# Datalogger_Shield_RTC.net
KiCad netlist of a schematic drawn in EAGLE
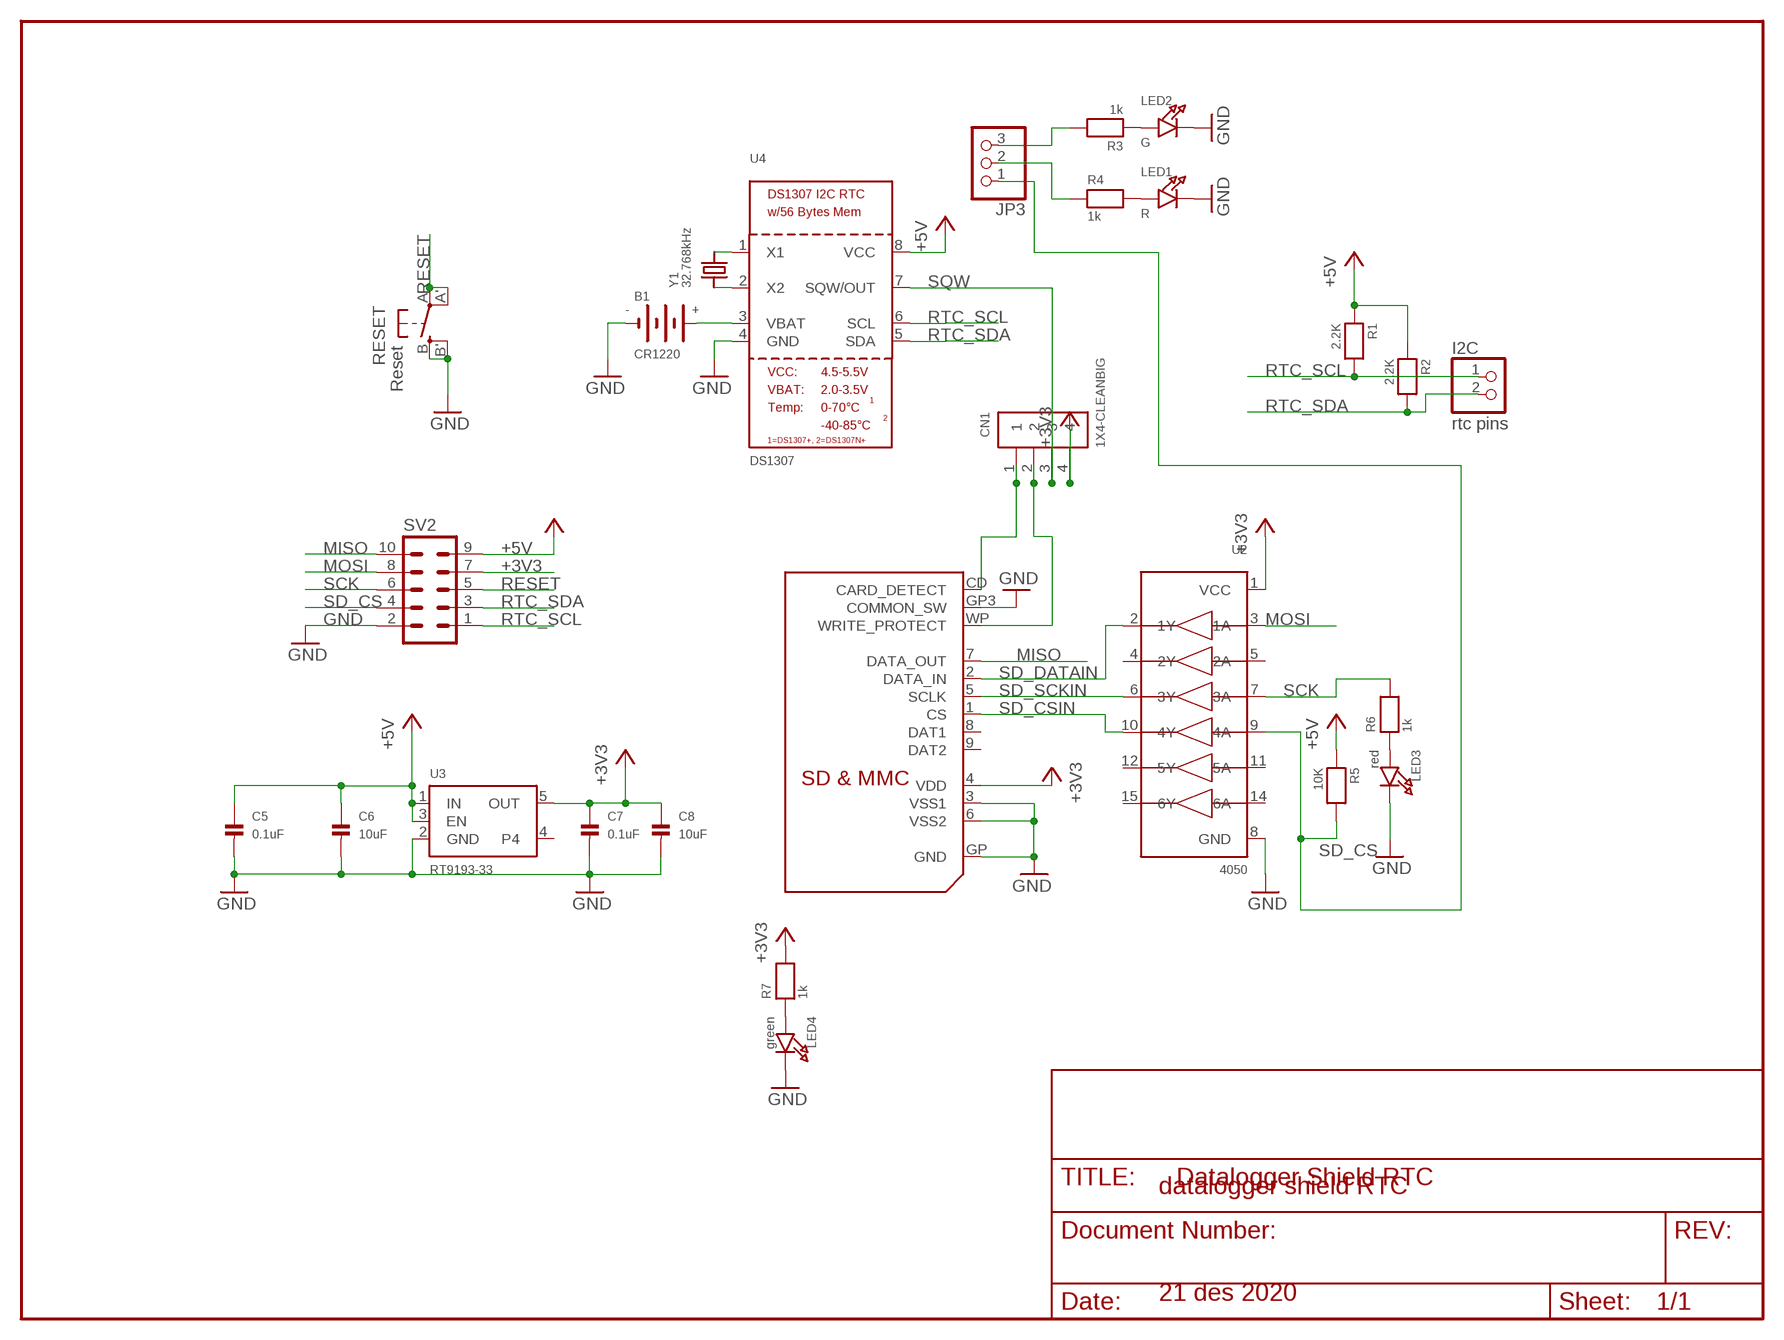
[diagram p0: schematic, sheet 1]

(export (version "E")
  (design (tool "Eeschema 10.0.6"))
  (components
    (comp (ref "B1")
      (value "CR1220")
      (footprint "eagle-import:CR1220")
      (libsource (lib "eagle-import") (part "BATTERYCR1220_SMT"))
    )
    (comp (ref "C5")
      (value "0.1uF")
      (footprint "eagle-import:0805")
      (libsource (lib "eagle-import") (part "CAP_CERAMIC0805"))
    )
    (comp (ref "C6")
      (value "10uF")
      (footprint "eagle-import:0805")
      (libsource (lib "eagle-import") (part "CAP_CERAMIC0805"))
    )
    (comp (ref "C7")
      (value "0.1uF")
      (footprint "eagle-import:0805")
      (libsource (lib "eagle-import") (part "CAP_CERAMIC0805"))
    )
    (comp (ref "C8")
      (value "10uF")
      (footprint "eagle-import:0805")
      (libsource (lib "eagle-import") (part "CAP_CERAMIC0805"))
    )
    (comp (ref "CN1")
      (value "1X4-CLEANBIG")
      (footprint "eagle-import:1X04-CLEANBIG")
      (libsource (lib "eagle-import") (part "1X4-CLEANBIG"))
    )
    (comp (ref "I2C")
      (value "rtc pins")
      (footprint "eagle-import:1X02")
      (libsource (lib "eagle-import") (part "PINHD-1X2"))
    )
    (comp (ref "JP3")
      (value "HEADER-1X3ROUND")
      (footprint "eagle-import:1X03_ROUND")
      (libsource (lib "eagle-import") (part "HEADER-1X3ROUND"))
    )
    (comp (ref "LED1")
      (value "R")
      (footprint "eagle-import:CHIPLED_0805")
      (libsource (lib "eagle-import") (part "LED0805"))
    )
    (comp (ref "LED2")
      (value "G")
      (footprint "eagle-import:CHIPLED_0805")
      (libsource (lib "eagle-import") (part "LED0805"))
    )
    (comp (ref "LED3")
      (value "red")
      (footprint "eagle-import:CHIPLED_0805")
      (libsource (lib "eagle-import") (part "LED0805"))
    )
    (comp (ref "LED4")
      (value "green")
      (footprint "eagle-import:CHIPLED_0805")
      (libsource (lib "eagle-import") (part "LED0805"))
    )
    (comp (ref "R1")
      (value "2.2K")
      (footprint "eagle-import:0805")
      (libsource (lib "eagle-import") (part "RESISTOR0805"))
    )
    (comp (ref "R2")
      (value "2.2K")
      (footprint "eagle-import:0805")
      (libsource (lib "eagle-import") (part "RESISTOR0805"))
    )
    (comp (ref "R3")
      (value "1k")
      (footprint "eagle-import:0805")
      (libsource (lib "eagle-import") (part "RESISTOR0805"))
    )
    (comp (ref "R4")
      (value "1k")
      (footprint "eagle-import:0805")
      (libsource (lib "eagle-import") (part "RESISTOR0805"))
    )
    (comp (ref "R5")
      (value "10K")
      (footprint "eagle-import:0805")
      (libsource (lib "eagle-import") (part "RESISTOR0805"))
    )
    (comp (ref "R6")
      (value "1k")
      (footprint "eagle-import:0805")
      (libsource (lib "eagle-import") (part "RESISTOR0805"))
    )
    (comp (ref "R7")
      (value "1k")
      (footprint "eagle-import:0805")
      (libsource (lib "eagle-import") (part "RESISTOR0805"))
    )
    (comp (ref "RESET")
      (value "Reset")
      (footprint "eagle-import:EVQ-Q2")
      (libsource (lib "eagle-import") (part "SPST_TACT-EVQQ2"))
    )
    (comp (ref "SV2")
      (value "MA05-2")
      (footprint "eagle-import:MA05-2")
      (libsource (lib "eagle-import") (part "MA05-2"))
    )
    (comp (ref "U$2")
      (value "SDMMC06132")
      (footprint "eagle-import:06132")
      (libsource (lib "eagle-import") (part "SDMMC06132"))
    )
    (comp (ref "U2")
      (value "4050")
      (footprint "eagle-import:SOIC16")
      (libsource (lib "eagle-import") (part "74HC4050D"))
    )
    (comp (ref "U3")
      (value "RT9193-33")
      (footprint "eagle-import:SOT23-5")
      (libsource (lib "eagle-import") (part "VREG_SOT23-5"))
    )
    (comp (ref "U4")
      (value "DS1307")
      (footprint "eagle-import:SOIC8_150MIL")
      (fields (field (name "SPICEPREFIX") "X"))
      (libsource (lib "eagle-import") (part "RTC_DS1307"))
    )
    (comp (ref "Y1")
      (value "32.768kHz")
      (footprint "eagle-import:CRYSTAL_8X3.8")
      (libsource (lib "eagle-import") (part "CRYSTAL8X3.8SMT"))
    )
  )
  (nets
    (net (code "1") (name "+3V3") (class "Default")
      (node (ref "C7") (pin "1") (pinfunction "P$1_1") (pintype "passive"))
      (node (ref "C8") (pin "1") (pinfunction "P$1_1") (pintype "passive"))
      (node (ref "CN1") (pin "4") (pinfunction "4_4") (pintype "bidirectional"))
      (node (ref "R7") (pin "2") (pinfunction "2_2") (pintype "passive"))
      (node (ref "SV2") (pin "7") (pinfunction "7_7") (pintype "passive"))
      (node (ref "U$2") (pin "4") (pinfunction "VDD_4") (pintype "power_in"))
      (node (ref "U2") (pin "1") (pinfunction "VCC_1") (pintype "bidirectional"))
      (node (ref "U3") (pin "5") (pinfunction "OUT_5") (pintype "bidirectional"))
    )
    (net (code "2") (name "+5V") (class "Default")
      (node (ref "C5") (pin "1") (pinfunction "P$1_1") (pintype "passive"))
      (node (ref "C6") (pin "1") (pinfunction "P$1_1") (pintype "passive"))
      (node (ref "R1") (pin "1") (pinfunction "1_1") (pintype "passive"))
      (node (ref "R2") (pin "1") (pinfunction "1_1") (pintype "passive"))
      (node (ref "R5") (pin "1") (pinfunction "1_1") (pintype "passive"))
      (node (ref "SV2") (pin "9") (pinfunction "9_9") (pintype "passive"))
      (node (ref "U3") (pin "1") (pinfunction "IN_1") (pintype "bidirectional"))
      (node (ref "U3") (pin "3") (pinfunction "EN_3") (pintype "bidirectional"))
      (node (ref "U4") (pin "8") (pinfunction "VCC_8") (pintype "bidirectional"))
    )
    (net (code "3") (name "/MISO") (class "Default")
      (node (ref "SV2") (pin "10") (pinfunction "10_10") (pintype "passive"))
      (node (ref "U$2") (pin "7") (pinfunction "DATA_OUT_7") (pintype "output"))
    )
    (net (code "4") (name "/MOSI") (class "Default")
      (node (ref "SV2") (pin "8") (pinfunction "8_8") (pintype "passive"))
      (node (ref "U2") (pin "3") (pinfunction "1A_3") (pintype "bidirectional"))
    )
    (net (code "5") (name "/RESET") (class "Default")
      (node (ref "RESET") (pin "A") (pinfunction "P_A") (pintype "passive"))
      (node (ref "RESET") (pin "A'") (pinfunction "P1_A'") (pintype "passive"))
      (node (ref "SV2") (pin "5") (pinfunction "5_5") (pintype "passive"))
    )
    (net (code "6") (name "/RTC_SCL") (class "Default")
      (node (ref "I2C") (pin "1") (pinfunction "1_1") (pintype "passive"))
      (node (ref "R1") (pin "2") (pinfunction "2_2") (pintype "passive"))
      (node (ref "SV2") (pin "1") (pinfunction "1_1") (pintype "passive"))
      (node (ref "U4") (pin "6") (pinfunction "SCL_6") (pintype "bidirectional"))
    )
    (net (code "7") (name "/RTC_SDA") (class "Default")
      (node (ref "I2C") (pin "2") (pinfunction "2_2") (pintype "passive"))
      (node (ref "R2") (pin "2") (pinfunction "2_2") (pintype "passive"))
      (node (ref "SV2") (pin "3") (pinfunction "3_3") (pintype "passive"))
      (node (ref "U4") (pin "5") (pinfunction "SDA_5") (pintype "bidirectional"))
    )
    (net (code "8") (name "/SCK") (class "Default")
      (node (ref "R6") (pin "2") (pinfunction "2_2") (pintype "passive"))
      (node (ref "SV2") (pin "6") (pinfunction "6_6") (pintype "passive"))
      (node (ref "U2") (pin "7") (pinfunction "3A_7") (pintype "bidirectional"))
    )
    (net (code "9") (name "/SD_CS") (class "Default")
      (node (ref "JP3") (pin "1") (pinfunction "1_1") (pintype "passive"))
      (node (ref "R5") (pin "2") (pinfunction "2_2") (pintype "passive"))
      (node (ref "SV2") (pin "4") (pinfunction "4_4") (pintype "passive"))
      (node (ref "U2") (pin "9") (pinfunction "4A_9") (pintype "bidirectional"))
    )
    (net (code "10") (name "/SD_CSIN") (class "Default")
      (node (ref "U$2") (pin "1") (pinfunction "CS_1") (pintype "input"))
      (node (ref "U2") (pin "10") (pinfunction "4Y_10") (pintype "bidirectional"))
    )
    (net (code "11") (name "/SD_DATAIN") (class "Default")
      (node (ref "U$2") (pin "2") (pinfunction "DATA_IN_2") (pintype "input"))
      (node (ref "U2") (pin "2") (pinfunction "1Y_2") (pintype "bidirectional"))
    )
    (net (code "12") (name "/SD_SCKIN") (class "Default")
      (node (ref "U$2") (pin "5") (pinfunction "SCLK_5") (pintype "input"))
      (node (ref "U2") (pin "6") (pinfunction "3Y_6") (pintype "bidirectional"))
    )
    (net (code "13") (name "/SQW") (class "Default")
      (node (ref "CN1") (pin "3") (pinfunction "3_3") (pintype "bidirectional"))
      (node (ref "U4") (pin "7") (pinfunction "SQW/OUT_7") (pintype "bidirectional"))
    )
    (net (code "14") (name "GND") (class "Default")
      (node (ref "B1") (pin "-") (pinfunction "-_-") (pintype "passive"))
      (node (ref "C5") (pin "2") (pinfunction "P$2_2") (pintype "passive"))
      (node (ref "C6") (pin "2") (pinfunction "P$2_2") (pintype "passive"))
      (node (ref "C7") (pin "2") (pinfunction "P$2_2") (pintype "passive"))
      (node (ref "C8") (pin "2") (pinfunction "P$2_2") (pintype "passive"))
      (node (ref "LED1") (pin "C") (pinfunction "C_C") (pintype "passive"))
      (node (ref "LED2") (pin "C") (pinfunction "C_C") (pintype "passive"))
      (node (ref "LED3") (pin "C") (pinfunction "C_C") (pintype "passive"))
      (node (ref "LED4") (pin "C") (pinfunction "C_C") (pintype "passive"))
      (node (ref "RESET") (pin "B") (pinfunction "S_B") (pintype "passive"))
      (node (ref "RESET") (pin "B'") (pinfunction "S1_B'") (pintype "passive"))
      (node (ref "SV2") (pin "2") (pinfunction "2_2") (pintype "passive"))
      (node (ref "U$2") (pin "3") (pinfunction "VSS1_3") (pintype "power_in"))
      (node (ref "U$2") (pin "6") (pinfunction "VSS2_6") (pintype "power_in"))
      (node (ref "U$2") (pin "GP") (pinfunction "GND_GP") (pintype "power_in"))
      (node (ref "U$2") (pin "GP3") (pinfunction "COMMON_SW_GP3") (pintype "passive"))
      (node (ref "U2") (pin "8") (pinfunction "GND_8") (pintype "bidirectional"))
      (node (ref "U3") (pin "2") (pinfunction "GND_2") (pintype "bidirectional"))
      (node (ref "U4") (pin "4") (pinfunction "GND_4") (pintype "bidirectional"))
    )
    (net (code "15") (name "Net-(B1-+)") (class "Default")
      (node (ref "B1") (pin "+$1") (pinfunction "+_+$1") (pintype "passive"))
      (node (ref "U4") (pin "3") (pinfunction "VBAT_3") (pintype "bidirectional"))
    )
    (net (code "16") (name "Net-(JP3-Pad2)") (class "Default")
      (node (ref "JP3") (pin "2") (pinfunction "2_2") (pintype "passive"))
      (node (ref "R4") (pin "1") (pinfunction "1_1") (pintype "passive"))
    )
    (net (code "17") (name "Net-(JP3-Pad3)") (class "Default")
      (node (ref "JP3") (pin "3") (pinfunction "3_3") (pintype "passive"))
      (node (ref "R3") (pin "2") (pinfunction "2_2") (pintype "passive"))
    )
    (net (code "18") (name "Net-(LED1-PadA)") (class "Default")
      (node (ref "LED1") (pin "A") (pinfunction "A_A") (pintype "passive"))
      (node (ref "R4") (pin "2") (pinfunction "2_2") (pintype "passive"))
    )
    (net (code "19") (name "Net-(LED2-PadA)") (class "Default")
      (node (ref "LED2") (pin "A") (pinfunction "A_A") (pintype "passive"))
      (node (ref "R3") (pin "1") (pinfunction "1_1") (pintype "passive"))
    )
    (net (code "20") (name "Net-(LED3-PadA)") (class "Default")
      (node (ref "LED3") (pin "A") (pinfunction "A_A") (pintype "passive"))
      (node (ref "R6") (pin "1") (pinfunction "1_1") (pintype "passive"))
    )
    (net (code "21") (name "Net-(LED4-PadA)") (class "Default")
      (node (ref "LED4") (pin "A") (pinfunction "A_A") (pintype "passive"))
      (node (ref "R7") (pin "1") (pinfunction "1_1") (pintype "passive"))
    )
    (net (code "22") (name "Net-(U$2-CARD_DETECT)") (class "Default")
      (node (ref "CN1") (pin "1") (pinfunction "1_1") (pintype "bidirectional"))
      (node (ref "U$2") (pin "CD") (pinfunction "CARD_DETECT_CD") (pintype "passive"))
    )
    (net (code "23") (name "Net-(U$2-WRITE_PROTECT)") (class "Default")
      (node (ref "CN1") (pin "2") (pinfunction "2_2") (pintype "bidirectional"))
      (node (ref "U$2") (pin "WP") (pinfunction "WRITE_PROTECT_WP") (pintype "passive"))
    )
    (net (code "24") (name "Net-(U4-X1)") (class "Default")
      (node (ref "U4") (pin "1") (pinfunction "X1_1") (pintype "bidirectional"))
      (node (ref "Y1") (pin "P$4") (pinfunction "2_P$4") (pintype "passive"))
    )
    (net (code "25") (name "Net-(U4-X2)") (class "Default")
      (node (ref "U4") (pin "2") (pinfunction "X2_2") (pintype "bidirectional"))
      (node (ref "Y1") (pin "P$1") (pinfunction "1_P$1") (pintype "passive"))
    )
    (net (code "26") (name "unconnected-(U$2-DAT1-Pad8)") (class "Default")
      (node (ref "U$2") (pin "8") (pinfunction "DAT1_8") (pintype "bidirectional"))
    )
    (net (code "27") (name "unconnected-(U$2-DAT2-Pad9)") (class "Default")
      (node (ref "U$2") (pin "9") (pinfunction "DAT2_9") (pintype "bidirectional"))
    )
    (net (code "28") (name "unconnected-(U2-2A-Pad5)") (class "Default")
      (node (ref "U2") (pin "5") (pinfunction "2A_5") (pintype "bidirectional"))
    )
    (net (code "29") (name "unconnected-(U2-2Y-Pad4)") (class "Default")
      (node (ref "U2") (pin "4") (pinfunction "2Y_4") (pintype "bidirectional"))
    )
    (net (code "30") (name "unconnected-(U2-5A-Pad11)") (class "Default")
      (node (ref "U2") (pin "11") (pinfunction "5A_11") (pintype "bidirectional"))
    )
    (net (code "31") (name "unconnected-(U2-5Y-Pad12)") (class "Default")
      (node (ref "U2") (pin "12") (pinfunction "5Y_12") (pintype "bidirectional"))
    )
    (net (code "32") (name "unconnected-(U2-6A-Pad14)") (class "Default")
      (node (ref "U2") (pin "14") (pinfunction "6A_14") (pintype "bidirectional"))
    )
    (net (code "33") (name "unconnected-(U2-6Y-Pad15)") (class "Default")
      (node (ref "U2") (pin "15") (pinfunction "6Y_15") (pintype "bidirectional"))
    )
    (net (code "34") (name "unconnected-(U3-P4-Pad4)") (class "Default")
      (node (ref "U3") (pin "4") (pinfunction "P4_4") (pintype "bidirectional"))
    )
  )
)
